# Sheet1_1.net
KiCad netlist of a schematic drawn in Altium Designer
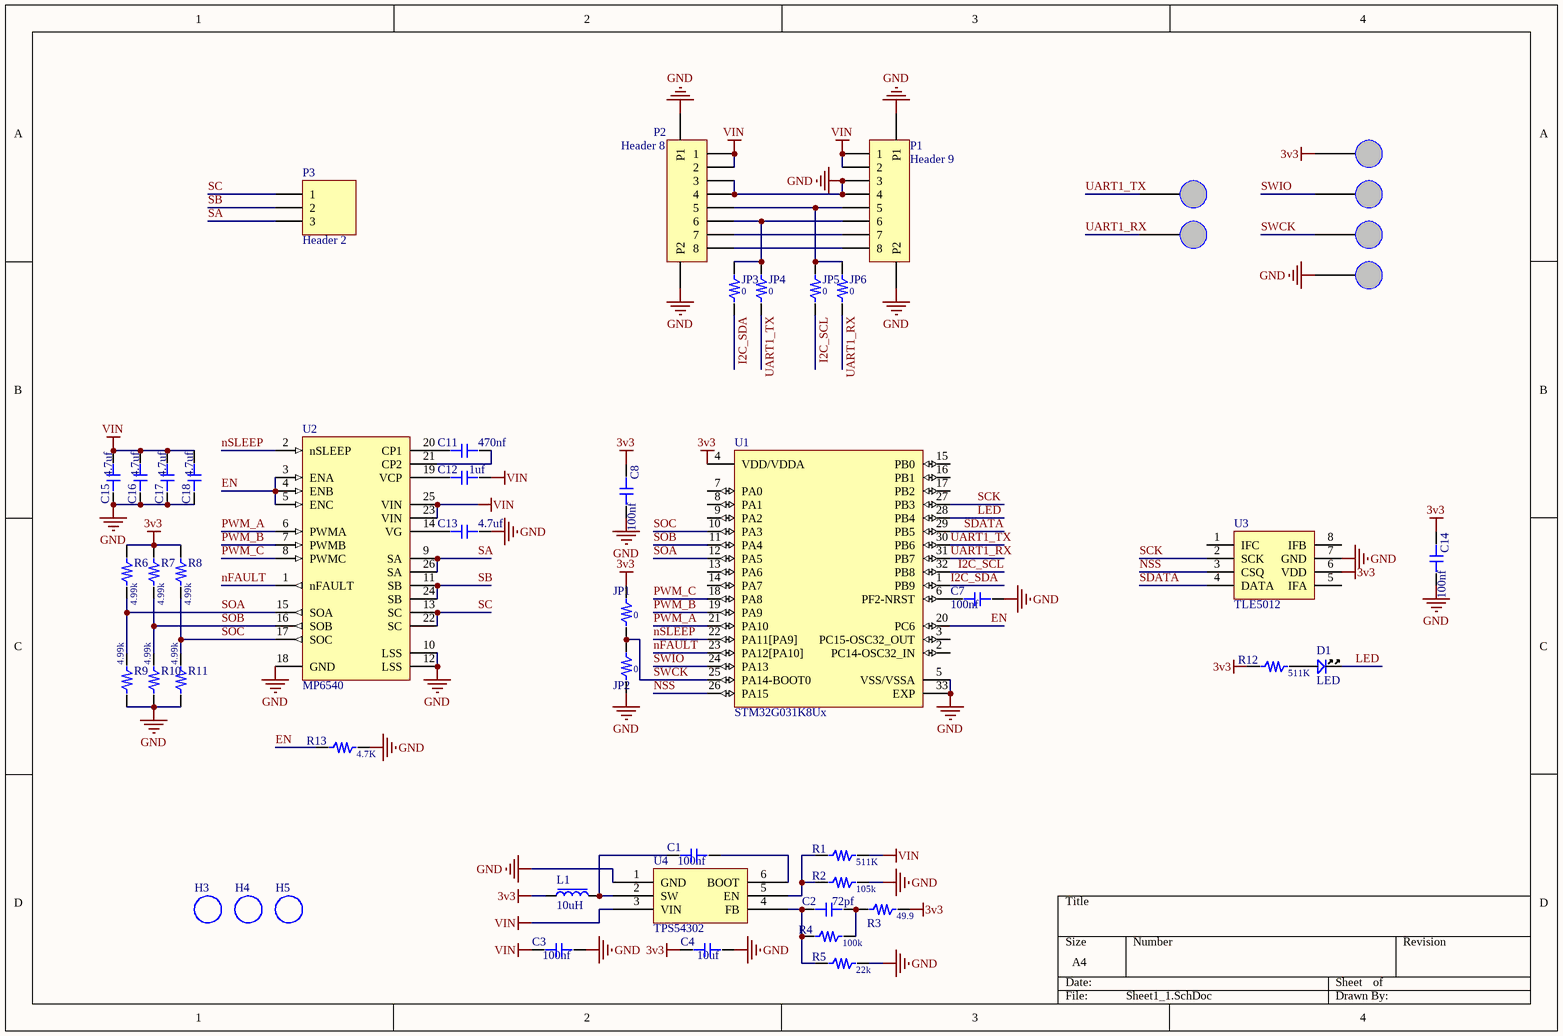
[diagram p0: Sheet1_1.SchDoc]

(export (version "E")
  (design (tool "Eeschema 10.0.6"))
  (components
    (comp (ref "3V3")
      (value "solder_pad")
      (footprint "solder_pad_1")
      (libsource (lib "zjti_lib") (part "solder_pad"))
    )
    (comp (ref "C1")
      (value "100nf")
      (footprint "C_0402")
      (fields (field (name "Comment") "C_0603"))
      (libsource (lib "zjti_lib") (part "C"))
    )
    (comp (ref "C2")
      (value "72pf")
      (footprint "C_0402")
      (fields (field (name "Comment") "C_0603"))
      (libsource (lib "zjti_lib") (part "C"))
    )
    (comp (ref "C3")
      (value "100nf")
      (footprint "C_0402")
      (fields (field (name "Comment") "C_0603"))
      (libsource (lib "zjti_lib") (part "C"))
    )
    (comp (ref "C4")
      (value "10uf")
      (footprint "C_0603")
      (fields (field (name "Comment") "C_0603"))
      (libsource (lib "zjti_lib") (part "C"))
    )
    (comp (ref "C7")
      (value "100nf")
      (footprint "C_0402")
      (fields (field (name "Comment") "C_0603"))
      (libsource (lib "zjti_lib") (part "C"))
    )
    (comp (ref "C8")
      (value "100nf")
      (footprint "C_0402")
      (fields (field (name "Comment") "C_0603"))
      (libsource (lib "zjti_lib") (part "C"))
    )
    (comp (ref "C11")
      (value "470nf")
      (footprint "C_0402")
      (fields (field (name "Comment") "C_0603"))
      (libsource (lib "zjti_lib") (part "C"))
    )
    (comp (ref "C12")
      (value "1uf")
      (footprint "C_0402")
      (fields (field (name "Comment") "C_0603"))
      (libsource (lib "zjti_lib") (part "C"))
    )
    (comp (ref "C13")
      (value "4.7uf")
      (footprint "C_0402")
      (fields (field (name "Comment") "C_0603"))
      (libsource (lib "zjti_lib") (part "C"))
    )
    (comp (ref "C14")
      (value "100nf")
      (footprint "C_0402")
      (fields (field (name "Comment") "C_0603"))
      (libsource (lib "zjti_lib") (part "C"))
    )
    (comp (ref "C15")
      (value "4.7uf")
      (footprint "C_0805")
      (fields (field (name "Comment") "C_0603"))
      (libsource (lib "zjti_lib") (part "C"))
    )
    (comp (ref "C16")
      (value "4.7uf")
      (footprint "C_0805")
      (fields (field (name "Comment") "C_0603"))
      (libsource (lib "zjti_lib") (part "C"))
    )
    (comp (ref "C17")
      (value "4.7uf")
      (footprint "C_0805")
      (fields (field (name "Comment") "C_0603"))
      (libsource (lib "zjti_lib") (part "C"))
    )
    (comp (ref "C18")
      (value "4.7uf")
      (footprint "C_0805")
      (fields (field (name "Comment") "C_0603"))
      (libsource (lib "zjti_lib") (part "C"))
    )
    (comp (ref "CK")
      (value "solder_pad")
      (footprint "solder_pad_1")
      (libsource (lib "zjti_lib") (part "solder_pad"))
    )
    (comp (ref "D1") (value "LED") (footprint "LED_0603") (libsource (lib "zjti_lib") (part "LED_SMD")))
    (comp (ref "GND")
      (value "solder_pad")
      (footprint "solder_pad_1")
      (libsource (lib "zjti_lib") (part "solder_pad"))
    )
    (comp (ref "H3")
      (value "~")
      (footprint "M3 Hole")
      (description "M3 Hole with no copper")
      (libsource (lib "CustomComponents") (part "M3 Hole"))
    )
    (comp (ref "H4")
      (value "~")
      (footprint "M3 Hole")
      (description "M3 Hole with no copper")
      (libsource (lib "CustomComponents") (part "M3 Hole"))
    )
    (comp (ref "H5")
      (value "~")
      (footprint "M3 Hole")
      (description "M3 Hole with no copper")
      (libsource (lib "CustomComponents") (part "M3 Hole"))
    )
    (comp (ref "IO")
      (value "solder_pad")
      (footprint "solder_pad_1")
      (libsource (lib "zjti_lib") (part "solder_pad"))
    )
    (comp (ref "JP1")
      (value "0")
      (footprint "R_0402")
      (fields (field (name "Comment") "R_0603"))
      (libsource (lib "zjti_lib") (part "R"))
    )
    (comp (ref "JP2")
      (value "0")
      (footprint "R_0402")
      (fields (field (name "Comment") "R_0603"))
      (libsource (lib "zjti_lib") (part "R"))
    )
    (comp (ref "JP3")
      (value "0")
      (footprint "R_0402")
      (fields (field (name "Comment") "R_0603"))
      (libsource (lib "zjti_lib") (part "R"))
    )
    (comp (ref "JP4")
      (value "0")
      (footprint "R_0402")
      (fields (field (name "Comment") "R_0603"))
      (libsource (lib "zjti_lib") (part "R"))
    )
    (comp (ref "JP5")
      (value "0")
      (footprint "R_0402")
      (fields (field (name "Comment") "R_0603"))
      (libsource (lib "zjti_lib") (part "R"))
    )
    (comp (ref "JP6")
      (value "0")
      (footprint "R_0402")
      (fields (field (name "Comment") "R_0603"))
      (libsource (lib "zjti_lib") (part "R"))
    )
    (comp (ref "L1")
      (value "10uH")
      (footprint "NR3015")
      (description "NR功率电感")
      (libsource (lib "zjti_lib") (part "L-NR"))
    )
    (comp (ref "P1")
      (value "Header 9")
      (footprint "JST_SM08B-SRSS-TB(LF)(SN)")
      (description "Header, 5-Pin")
      (fields (field (name "PUBLISHER") "Altium Limited"))
      (libsource (lib "zjti_lib") (part "Header 8"))
    )
    (comp (ref "P2")
      (value "Header 8")
      (footprint "JST_SM08B-SRSS-TB(LF)(SN)")
      (description "Header, 5-Pin")
      (fields (field (name "PUBLISHER") "Altium Limited"))
      (libsource (lib "") (part "Header 8_1"))
    )
    (comp (ref "P3")
      (value "Header 2")
      (footprint "MOLEX_530480310")
      (description "Header, 2-Pin")
      (fields (field (name "PUBLISHER") "Altium Limited"))
      (libsource (lib "zjti_lib") (part "Header 3"))
    )
    (comp (ref "R1")
      (value "511K")
      (footprint "R_0402")
      (fields (field (name "Comment") "R_0603"))
      (libsource (lib "zjti_lib") (part "R"))
    )
    (comp (ref "R2")
      (value "105k")
      (footprint "R_0402")
      (fields (field (name "Comment") "R_0603"))
      (libsource (lib "zjti_lib") (part "R"))
    )
    (comp (ref "R3")
      (value "49.9")
      (footprint "R_0402")
      (fields (field (name "Comment") "R_0603"))
      (libsource (lib "zjti_lib") (part "R"))
    )
    (comp (ref "R4")
      (value "100k")
      (footprint "R_0402")
      (fields (field (name "Comment") "R_0603"))
      (libsource (lib "zjti_lib") (part "R"))
    )
    (comp (ref "R5")
      (value "22k")
      (footprint "R_0402")
      (fields (field (name "Comment") "R_0603"))
      (libsource (lib "zjti_lib") (part "R"))
    )
    (comp (ref "R6")
      (value "4.99k")
      (footprint "R_0402")
      (fields (field (name "Comment") "R_0603"))
      (libsource (lib "zjti_lib") (part "R"))
    )
    (comp (ref "R7")
      (value "4.99k")
      (footprint "R_0402")
      (fields (field (name "Comment") "R_0603"))
      (libsource (lib "zjti_lib") (part "R"))
    )
    (comp (ref "R8")
      (value "4.99k")
      (footprint "R_0402")
      (fields (field (name "Comment") "R_0603"))
      (libsource (lib "zjti_lib") (part "R"))
    )
    (comp (ref "R9")
      (value "4.99k")
      (footprint "R_0402")
      (fields (field (name "Comment") "R_0603"))
      (libsource (lib "zjti_lib") (part "R"))
    )
    (comp (ref "R10")
      (value "4.99k")
      (footprint "R_0402")
      (fields (field (name "Comment") "R_0603"))
      (libsource (lib "zjti_lib") (part "R"))
    )
    (comp (ref "R11")
      (value "4.99k")
      (footprint "R_0402")
      (fields (field (name "Comment") "R_0603"))
      (libsource (lib "zjti_lib") (part "R"))
    )
    (comp (ref "R12")
      (value "511K")
      (footprint "R_0402")
      (fields (field (name "Comment") "R_0603"))
      (libsource (lib "zjti_lib") (part "R"))
    )
    (comp (ref "R13")
      (value "4.7K")
      (footprint "R_0402")
      (fields (field (name "Comment") "R_0603"))
      (libsource (lib "zjti_lib") (part "R"))
    )
    (comp (ref "RX")
      (value "solder_pad")
      (footprint "solder_pad_1")
      (libsource (lib "zjti_lib") (part "solder_pad"))
    )
    (comp (ref "TX")
      (value "solder_pad")
      (footprint "solder_pad_1")
      (libsource (lib "zjti_lib") (part "solder_pad"))
    )
    (comp (ref "U1")
      (value "STM32G031K8Ux")
      (footprint "QFN32")
      (fields (field (name "MP") "STM32G431KBU3") (field (name "MF") "STMicroelectronics"))
      (libsource (lib "zjti_lib") (part "STM32G031KBUx"))
    )
    (comp (ref "U2")
      (value "MP6540")
      (footprint "QFN26-MPS")
      (fields (field (name "MP") "STM32G431KBU3") (field (name "MF") "STMicroelectronics"))
      (libsource (lib "zjti_lib") (part "MP6540"))
    )
    (comp (ref "U3") (value "TLE5012") (footprint "SOIC8") (libsource (lib "zjti_lib") (part "TLE5012")))
    (comp (ref "U4") (value "TPS54302") (footprint "SOT-23-6") (libsource (lib "zjti_lib") (part "TPS54302")))
  )
  (nets
    (net (code "1") (name "/EN") (class "Default")
      (node (ref "R13") (pin "1") (pinfunction "1_1") (pintype "passive"))
      (node (ref "U1") (pin "20") (pinfunction "PC6_20") (pintype "bidirectional"))
      (node (ref "U2") (pin "3") (pinfunction "ENA_3") (pintype "input"))
      (node (ref "U2") (pin "4") (pinfunction "ENB_4") (pintype "input"))
      (node (ref "U2") (pin "5") (pinfunction "ENC_5") (pintype "input"))
    )
    (net (code "2") (name "/I2C_SCL") (class "Default")
      (node (ref "JP5") (pin "2") (pinfunction "2_2") (pintype "passive"))
      (node (ref "U1") (pin "32") (pinfunction "PB8_32") (pintype "bidirectional"))
    )
    (net (code "3") (name "/I2C_SDA") (class "Default")
      (node (ref "JP3") (pin "2") (pinfunction "2_2") (pintype "passive"))
      (node (ref "U1") (pin "1") (pinfunction "PB9_1") (pintype "bidirectional"))
    )
    (net (code "4") (name "/LED") (class "Default")
      (node (ref "D1") (pin "C") (pintype "passive"))
      (node (ref "U1") (pin "28") (pinfunction "PB4_28") (pintype "bidirectional"))
    )
    (net (code "5") (name "/NSS") (class "Default")
      (node (ref "U1") (pin "26") (pinfunction "PA15_26") (pintype "bidirectional"))
      (node (ref "U3") (pin "3") (pinfunction "CSQ_3") (pintype "passive"))
    )
    (net (code "6") (name "/PWM_A") (class "Default")
      (node (ref "U1") (pin "21") (pinfunction "PA10_21") (pintype "bidirectional"))
      (node (ref "U2") (pin "6") (pinfunction "PWMA_6") (pintype "input"))
    )
    (net (code "7") (name "/PWM_B") (class "Default")
      (node (ref "U1") (pin "19") (pinfunction "PA9_19") (pintype "bidirectional"))
      (node (ref "U2") (pin "7") (pinfunction "PWMB_7") (pintype "input"))
    )
    (net (code "8") (name "/PWM_C") (class "Default")
      (node (ref "U1") (pin "18") (pinfunction "PA8_18") (pintype "bidirectional"))
      (node (ref "U2") (pin "8") (pinfunction "PWMC_8") (pintype "input"))
    )
    (net (code "9") (name "/SA") (class "Default")
      (node (ref "P3") (pin "3") (pinfunction "3_3") (pintype "passive"))
      (node (ref "U2") (pin "26") (pinfunction "SA_26") (pintype "power_in"))
      (node (ref "U2") (pin "9") (pinfunction "SA_9") (pintype "power_in"))
    )
    (net (code "10") (name "/SB") (class "Default")
      (node (ref "P3") (pin "2") (pinfunction "2_2") (pintype "passive"))
      (node (ref "U2") (pin "11") (pinfunction "SB_11") (pintype "power_in"))
      (node (ref "U2") (pin "24") (pinfunction "SB_24") (pintype "power_in"))
    )
    (net (code "11") (name "/SC") (class "Default")
      (node (ref "P3") (pin "1") (pinfunction "1_1") (pintype "passive"))
      (node (ref "U2") (pin "13") (pinfunction "SC_13") (pintype "power_in"))
      (node (ref "U2") (pin "22") (pinfunction "SC_22") (pintype "power_in"))
    )
    (net (code "12") (name "/SCK") (class "Default")
      (node (ref "U1") (pin "27") (pinfunction "PB3_27") (pintype "bidirectional"))
      (node (ref "U3") (pin "2") (pinfunction "SCK_2") (pintype "passive"))
    )
    (net (code "13") (name "/SDATA") (class "Default")
      (node (ref "U1") (pin "29") (pinfunction "PB5_29") (pintype "bidirectional"))
      (node (ref "U3") (pin "4") (pinfunction "DATA_4") (pintype "passive"))
    )
    (net (code "14") (name "/SOA") (class "Default")
      (node (ref "R6") (pin "1") (pinfunction "1_1") (pintype "passive"))
      (node (ref "R9") (pin "2") (pinfunction "2_2") (pintype "passive"))
      (node (ref "U1") (pin "12") (pinfunction "PA5_12") (pintype "bidirectional"))
      (node (ref "U2") (pin "15") (pinfunction "SOA_15") (pintype "output"))
    )
    (net (code "15") (name "/SOB") (class "Default")
      (node (ref "R10") (pin "2") (pinfunction "2_2") (pintype "passive"))
      (node (ref "R7") (pin "1") (pinfunction "1_1") (pintype "passive"))
      (node (ref "U1") (pin "11") (pinfunction "PA4_11") (pintype "bidirectional"))
      (node (ref "U2") (pin "16") (pinfunction "SOB_16") (pintype "output"))
    )
    (net (code "16") (name "/SOC") (class "Default")
      (node (ref "R11") (pin "2") (pinfunction "2_2") (pintype "passive"))
      (node (ref "R8") (pin "1") (pinfunction "1_1") (pintype "passive"))
      (node (ref "U1") (pin "10") (pinfunction "PA3_10") (pintype "bidirectional"))
      (node (ref "U2") (pin "17") (pinfunction "SOC_17") (pintype "output"))
    )
    (net (code "17") (name "/SWCK") (class "Default")
      (node (ref "CK") (pin "1") (pinfunction "1_1") (pintype "passive"))
      (node (ref "JP1") (pin "1") (pinfunction "1_1") (pintype "passive"))
      (node (ref "JP2") (pin "2") (pinfunction "2_2") (pintype "passive"))
      (node (ref "U1") (pin "25") (pinfunction "PA14-BOOT0_25") (pintype "bidirectional"))
    )
    (net (code "18") (name "/SWIO") (class "Default")
      (node (ref "IO") (pin "1") (pinfunction "1_1") (pintype "passive"))
      (node (ref "U1") (pin "24") (pinfunction "PA13_24") (pintype "bidirectional"))
    )
    (net (code "19") (name "/UART1_RX") (class "Default")
      (node (ref "JP6") (pin "2") (pinfunction "2_2") (pintype "passive"))
      (node (ref "RX") (pin "1") (pinfunction "1_1") (pintype "passive"))
      (node (ref "U1") (pin "31") (pinfunction "PB7_31") (pintype "bidirectional"))
    )
    (net (code "20") (name "/UART1_TX") (class "Default")
      (node (ref "JP4") (pin "2") (pinfunction "2_2") (pintype "passive"))
      (node (ref "TX") (pin "1") (pinfunction "1_1") (pintype "passive"))
      (node (ref "U1") (pin "30") (pinfunction "PB6_30") (pintype "bidirectional"))
    )
    (net (code "21") (name "/nFAULT") (class "Default")
      (node (ref "U1") (pin "23") (pinfunction "PA12[PA10]_23") (pintype "bidirectional"))
      (node (ref "U2") (pin "1") (pinfunction "nFAULT_1") (pintype "output"))
    )
    (net (code "22") (name "/nSLEEP") (class "Default")
      (node (ref "U1") (pin "22") (pinfunction "PA11[PA9]_22") (pintype "bidirectional"))
      (node (ref "U2") (pin "2") (pinfunction "nSLEEP_2") (pintype "input"))
    )
    (net (code "23") (name "3v3") (class "Default")
      (node (ref "3V3") (pin "1") (pinfunction "1_1") (pintype "passive"))
      (node (ref "C14") (pin "1") (pinfunction "1_1") (pintype "passive"))
      (node (ref "C4") (pin "1") (pinfunction "1_1") (pintype "passive"))
      (node (ref "C8") (pin "1") (pinfunction "1_1") (pintype "passive"))
      (node (ref "JP1") (pin "2") (pinfunction "2_2") (pintype "passive"))
      (node (ref "L1") (pin "1") (pinfunction "1_1") (pintype "passive"))
      (node (ref "R12") (pin "1") (pinfunction "1_1") (pintype "passive"))
      (node (ref "R3") (pin "2") (pinfunction "2_2") (pintype "passive"))
      (node (ref "R6") (pin "2") (pinfunction "2_2") (pintype "passive"))
      (node (ref "R7") (pin "2") (pinfunction "2_2") (pintype "passive"))
      (node (ref "R8") (pin "2") (pinfunction "2_2") (pintype "passive"))
      (node (ref "U1") (pin "4") (pinfunction "VDD/VDDA_4") (pintype "power_in"))
      (node (ref "U3") (pin "6") (pinfunction "VDD_6") (pintype "passive"))
    )
    (net (code "24") (name "GND") (class "Default")
      (node (ref "C13") (pin "2") (pinfunction "2_2") (pintype "passive"))
      (node (ref "C14") (pin "2") (pinfunction "2_2") (pintype "passive"))
      (node (ref "C15") (pin "1") (pinfunction "1_1") (pintype "passive"))
      (node (ref "C16") (pin "1") (pinfunction "1_1") (pintype "passive"))
      (node (ref "C17") (pin "1") (pinfunction "1_1") (pintype "passive"))
      (node (ref "C18") (pin "1") (pinfunction "1_1") (pintype "passive"))
      (node (ref "C3") (pin "2") (pinfunction "2_2") (pintype "passive"))
      (node (ref "C4") (pin "2") (pinfunction "2_2") (pintype "passive"))
      (node (ref "C7") (pin "2") (pinfunction "2_2") (pintype "passive"))
      (node (ref "C8") (pin "2") (pinfunction "2_2") (pintype "passive"))
      (node (ref "GND") (pin "1") (pinfunction "1_1") (pintype "passive"))
      (node (ref "JP2") (pin "1") (pinfunction "1_1") (pintype "passive"))
      (node (ref "P1") (pin "3") (pinfunction "3_3") (pintype "passive"))
      (node (ref "P1") (pin "4") (pinfunction "4_4") (pintype "passive"))
      (node (ref "P1") (pin "P1") (pinfunction "P1_P1") (pintype "passive"))
      (node (ref "P1") (pin "P2") (pinfunction "P2_P2") (pintype "passive"))
      (node (ref "P2") (pin "3") (pinfunction "3_3") (pintype "passive"))
      (node (ref "P2") (pin "4") (pinfunction "4_4") (pintype "passive"))
      (node (ref "P2") (pin "P1") (pinfunction "P1_P1") (pintype "passive"))
      (node (ref "P2") (pin "P2") (pinfunction "P2_P2") (pintype "passive"))
      (node (ref "R10") (pin "1") (pinfunction "1_1") (pintype "passive"))
      (node (ref "R11") (pin "1") (pinfunction "1_1") (pintype "passive"))
      (node (ref "R13") (pin "2") (pinfunction "2_2") (pintype "passive"))
      (node (ref "R2") (pin "2") (pinfunction "2_2") (pintype "passive"))
      (node (ref "R5") (pin "2") (pinfunction "2_2") (pintype "passive"))
      (node (ref "R9") (pin "1") (pinfunction "1_1") (pintype "passive"))
      (node (ref "U1") (pin "33") (pinfunction "EXP_33") (pintype "power_in"))
      (node (ref "U1") (pin "5") (pinfunction "VSS/VSSA_5") (pintype "power_in"))
      (node (ref "U2") (pin "10") (pinfunction "LSS_10") (pintype "power_in"))
      (node (ref "U2") (pin "12") (pinfunction "LSS_12") (pintype "power_in"))
      (node (ref "U2") (pin "18") (pinfunction "GND_18") (pintype "power_in"))
      (node (ref "U3") (pin "7") (pinfunction "GND_7") (pintype "passive"))
      (node (ref "U4") (pin "1") (pinfunction "GND_1") (pintype "passive"))
    )
    (net (code "25") (name "Net-(C2-Pad2)") (class "Default")
      (node (ref "C2") (pin "2") (pinfunction "2_2") (pintype "passive"))
      (node (ref "R3") (pin "1") (pinfunction "1_1") (pintype "passive"))
      (node (ref "R4") (pin "2") (pinfunction "2_2") (pintype "passive"))
    )
    (net (code "26") (name "Net-(D1-PadA)") (class "Default")
      (node (ref "D1") (pin "A") (pintype "passive"))
      (node (ref "R12") (pin "2") (pinfunction "2_2") (pintype "passive"))
    )
    (net (code "27") (name "Net-(JP3-Pad1)") (class "Default")
      (node (ref "JP3") (pin "1") (pinfunction "1_1") (pintype "passive"))
      (node (ref "JP4") (pin "1") (pinfunction "1_1") (pintype "passive"))
      (node (ref "P1") (pin "6") (pinfunction "6_6") (pintype "passive"))
      (node (ref "P2") (pin "6") (pinfunction "6_6") (pintype "passive"))
    )
    (net (code "28") (name "Net-(JP5-Pad1)") (class "Default")
      (node (ref "JP5") (pin "1") (pinfunction "1_1") (pintype "passive"))
      (node (ref "JP6") (pin "1") (pinfunction "1_1") (pintype "passive"))
      (node (ref "P1") (pin "5") (pinfunction "5_5") (pintype "passive"))
      (node (ref "P2") (pin "5") (pinfunction "5_5") (pintype "passive"))
    )
    (net (code "29") (name "Net-(P1-Pad7)") (class "Default")
      (node (ref "P1") (pin "7") (pinfunction "7_7") (pintype "passive"))
      (node (ref "P2") (pin "7") (pinfunction "7_7") (pintype "passive"))
    )
    (net (code "30") (name "Net-(P1-Pad8)") (class "Default")
      (node (ref "P1") (pin "8") (pinfunction "8_8") (pintype "passive"))
      (node (ref "P2") (pin "8") (pinfunction "8_8") (pintype "passive"))
    )
    (net (code "31") (name "Net-(U1-PF2-NRST)") (class "Default")
      (node (ref "C7") (pin "1") (pinfunction "1_1") (pintype "passive"))
      (node (ref "U1") (pin "6") (pinfunction "PF2-NRST_6") (pintype "bidirectional"))
    )
    (net (code "32") (name "Net-(U2-CP1)") (class "Default")
      (node (ref "C11") (pin "1") (pinfunction "1_1") (pintype "passive"))
      (node (ref "U2") (pin "20") (pinfunction "CP1_20") (pintype "passive"))
    )
    (net (code "33") (name "Net-(U2-CP2)") (class "Default")
      (node (ref "C11") (pin "2") (pinfunction "2_2") (pintype "passive"))
      (node (ref "U2") (pin "21") (pinfunction "CP2_21") (pintype "passive"))
    )
    (net (code "34") (name "Net-(U2-VCP)") (class "Default")
      (node (ref "C12") (pin "1") (pinfunction "1_1") (pintype "passive"))
      (node (ref "U2") (pin "19") (pinfunction "VCP_19") (pintype "power_in"))
    )
    (net (code "35") (name "Net-(U2-VG)") (class "Default")
      (node (ref "C13") (pin "1") (pinfunction "1_1") (pintype "passive"))
      (node (ref "U2") (pin "14") (pinfunction "VG_14") (pintype "power_in"))
    )
    (net (code "36") (name "Net-(U4-BOOT)") (class "Default")
      (node (ref "C1") (pin "2") (pinfunction "2_2") (pintype "passive"))
      (node (ref "U4") (pin "6") (pinfunction "BOOT_6") (pintype "passive"))
    )
    (net (code "37") (name "Net-(U4-EN)") (class "Default")
      (node (ref "R1") (pin "1") (pinfunction "1_1") (pintype "passive"))
      (node (ref "R2") (pin "1") (pinfunction "1_1") (pintype "passive"))
      (node (ref "U4") (pin "5") (pinfunction "EN_5") (pintype "passive"))
    )
    (net (code "38") (name "Net-(U4-FB)") (class "Default")
      (node (ref "C2") (pin "1") (pinfunction "1_1") (pintype "passive"))
      (node (ref "R4") (pin "1") (pinfunction "1_1") (pintype "passive"))
      (node (ref "R5") (pin "1") (pinfunction "1_1") (pintype "passive"))
      (node (ref "U4") (pin "4") (pinfunction "FB_4") (pintype "passive"))
    )
    (net (code "39") (name "Net-(U4-SW)") (class "Default")
      (node (ref "C1") (pin "1") (pinfunction "1_1") (pintype "passive"))
      (node (ref "L1") (pin "2") (pinfunction "2_2") (pintype "passive"))
      (node (ref "U4") (pin "2") (pinfunction "SW_2") (pintype "passive"))
    )
    (net (code "40") (name "VIN") (class "Default")
      (node (ref "C12") (pin "2") (pinfunction "2_2") (pintype "passive"))
      (node (ref "C15") (pin "2") (pinfunction "2_2") (pintype "passive"))
      (node (ref "C16") (pin "2") (pinfunction "2_2") (pintype "passive"))
      (node (ref "C17") (pin "2") (pinfunction "2_2") (pintype "passive"))
      (node (ref "C18") (pin "2") (pinfunction "2_2") (pintype "passive"))
      (node (ref "C3") (pin "1") (pinfunction "1_1") (pintype "passive"))
      (node (ref "P1") (pin "1") (pinfunction "1_1") (pintype "passive"))
      (node (ref "P1") (pin "2") (pinfunction "2_2") (pintype "passive"))
      (node (ref "P2") (pin "1") (pinfunction "1_1") (pintype "passive"))
      (node (ref "P2") (pin "2") (pinfunction "2_2") (pintype "passive"))
      (node (ref "R1") (pin "2") (pinfunction "2_2") (pintype "passive"))
      (node (ref "U2") (pin "23") (pinfunction "VIN_23") (pintype "power_in"))
      (node (ref "U2") (pin "25") (pinfunction "VIN_25") (pintype "power_in"))
      (node (ref "U4") (pin "3") (pinfunction "VIN_3") (pintype "passive"))
    )
    (net (code "41") (name "unconnected-(U1-PA0-Pad7)") (class "Default")
      (node (ref "U1") (pin "7") (pinfunction "PA0_7") (pintype "bidirectional"))
    )
    (net (code "42") (name "unconnected-(U1-PA1-Pad8)") (class "Default")
      (node (ref "U1") (pin "8") (pinfunction "PA1_8") (pintype "bidirectional"))
    )
    (net (code "43") (name "unconnected-(U1-PA2-Pad9)") (class "Default")
      (node (ref "U1") (pin "9") (pinfunction "PA2_9") (pintype "bidirectional"))
    )
    (net (code "44") (name "unconnected-(U1-PA6-Pad13)") (class "Default")
      (node (ref "U1") (pin "13") (pinfunction "PA6_13") (pintype "bidirectional"))
    )
    (net (code "45") (name "unconnected-(U1-PA7-Pad14)") (class "Default")
      (node (ref "U1") (pin "14") (pinfunction "PA7_14") (pintype "bidirectional"))
    )
    (net (code "46") (name "unconnected-(U1-PB0-Pad15)") (class "Default")
      (node (ref "U1") (pin "15") (pinfunction "PB0_15") (pintype "bidirectional"))
    )
    (net (code "47") (name "unconnected-(U1-PB1-Pad16)") (class "Default")
      (node (ref "U1") (pin "16") (pinfunction "PB1_16") (pintype "bidirectional"))
    )
    (net (code "48") (name "unconnected-(U1-PB2-Pad17)") (class "Default")
      (node (ref "U1") (pin "17") (pinfunction "PB2_17") (pintype "bidirectional"))
    )
    (net (code "49") (name "unconnected-(U1-PC14-OSC32_IN-Pad2)") (class "Default")
      (node (ref "U1") (pin "2") (pinfunction "PC14-OSC32_IN_2") (pintype "bidirectional"))
    )
    (net (code "50") (name "unconnected-(U1-PC15-OSC32_OUT-Pad3)") (class "Default")
      (node (ref "U1") (pin "3") (pinfunction "PC15-OSC32_OUT_3") (pintype "bidirectional"))
    )
    (net (code "51") (name "unconnected-(U3-IFA-Pad5)") (class "Default")
      (node (ref "U3") (pin "5") (pinfunction "IFA_5") (pintype "passive"))
    )
    (net (code "52") (name "unconnected-(U3-IFB-Pad8)") (class "Default")
      (node (ref "U3") (pin "8") (pinfunction "IFB_8") (pintype "passive"))
    )
    (net (code "53") (name "unconnected-(U3-IFC-Pad1)") (class "Default")
      (node (ref "U3") (pin "1") (pinfunction "IFC_1") (pintype "passive"))
    )
  )
)
